# Power.net
KiCad netlist of a schematic drawn in Altium Designer
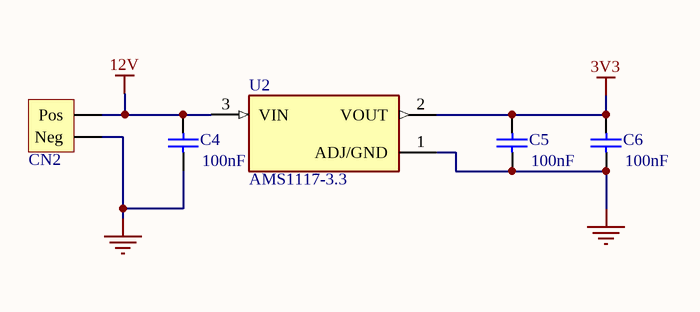
[diagram p0: Power.SchDoc]

(export (version "E")
  (design (tool "Eeschema 10.0.6"))
  (components
    (comp (ref "C4")
      (value "100nF")
      (footprint "0402")
      (fields (field (name "Comment") "Cap") (field (name "PUBLISHER") "Altium Limited"))
      (libsource (lib "Parts") (part "Cap"))
    )
    (comp (ref "C5")
      (value "100nF")
      (footprint "0402")
      (fields (field (name "Comment") "Cap") (field (name "PUBLISHER") "Altium Limited"))
      (libsource (lib "Parts") (part "Cap"))
    )
    (comp (ref "C6")
      (value "100nF")
      (footprint "0402")
      (fields (field (name "Comment") "Cap") (field (name "PUBLISHER") "Altium Limited"))
      (libsource (lib "Parts") (part "Cap"))
    )
    (comp (ref "CN2")
      (value "JST_Leads_In")
      (footprint "Power_Leads")
      (libsource (lib "Parts") (part "JST_Leads_In"))
    )
    (comp (ref "U2")
      (value "AMS1117-3.3")
      (footprint "SOT229P700X180-4N")
      (description "Sot223/Pkg 1-Amp 3.3-Volt Low Drop Out Voltage Regulatator")
      (fields (field (name "MF") "Advanced Monolithic Systems"))
      (libsource (lib "Parts") (part "AMS1117-3.3"))
    )
  )
  (nets
    (net (code "1") (name "3V3") (class "Default")
      (node (ref "C5") (pin "2") (pinfunction "2_2") (pintype "passive"))
      (node (ref "C6") (pin "2") (pinfunction "2_2") (pintype "passive"))
      (node (ref "U2") (pin "2") (pinfunction "VOUT_2") (pintype "output"))
    )
    (net (code "2") (name "12V") (class "Default")
      (node (ref "C4") (pin "2") (pinfunction "2_2") (pintype "passive"))
      (node (ref "CN2") (pin "A") (pinfunction "Pos_A") (pintype "passive"))
      (node (ref "U2") (pin "3") (pinfunction "VIN_3") (pintype "input"))
    )
    (net (code "3") (name "GND") (class "Default")
      (node (ref "C4") (pin "1") (pinfunction "1_1") (pintype "passive"))
      (node (ref "C5") (pin "1") (pinfunction "1_1") (pintype "passive"))
      (node (ref "C6") (pin "1") (pinfunction "1_1") (pintype "passive"))
      (node (ref "CN2") (pin "K") (pinfunction "Neg_K") (pintype "passive"))
      (node (ref "U2") (pin "1") (pinfunction "ADJ/GND_1") (pintype "power_in"))
    )
  )
)
